# DI_DO.net
KiCad netlist of a schematic drawn in Altium Designer
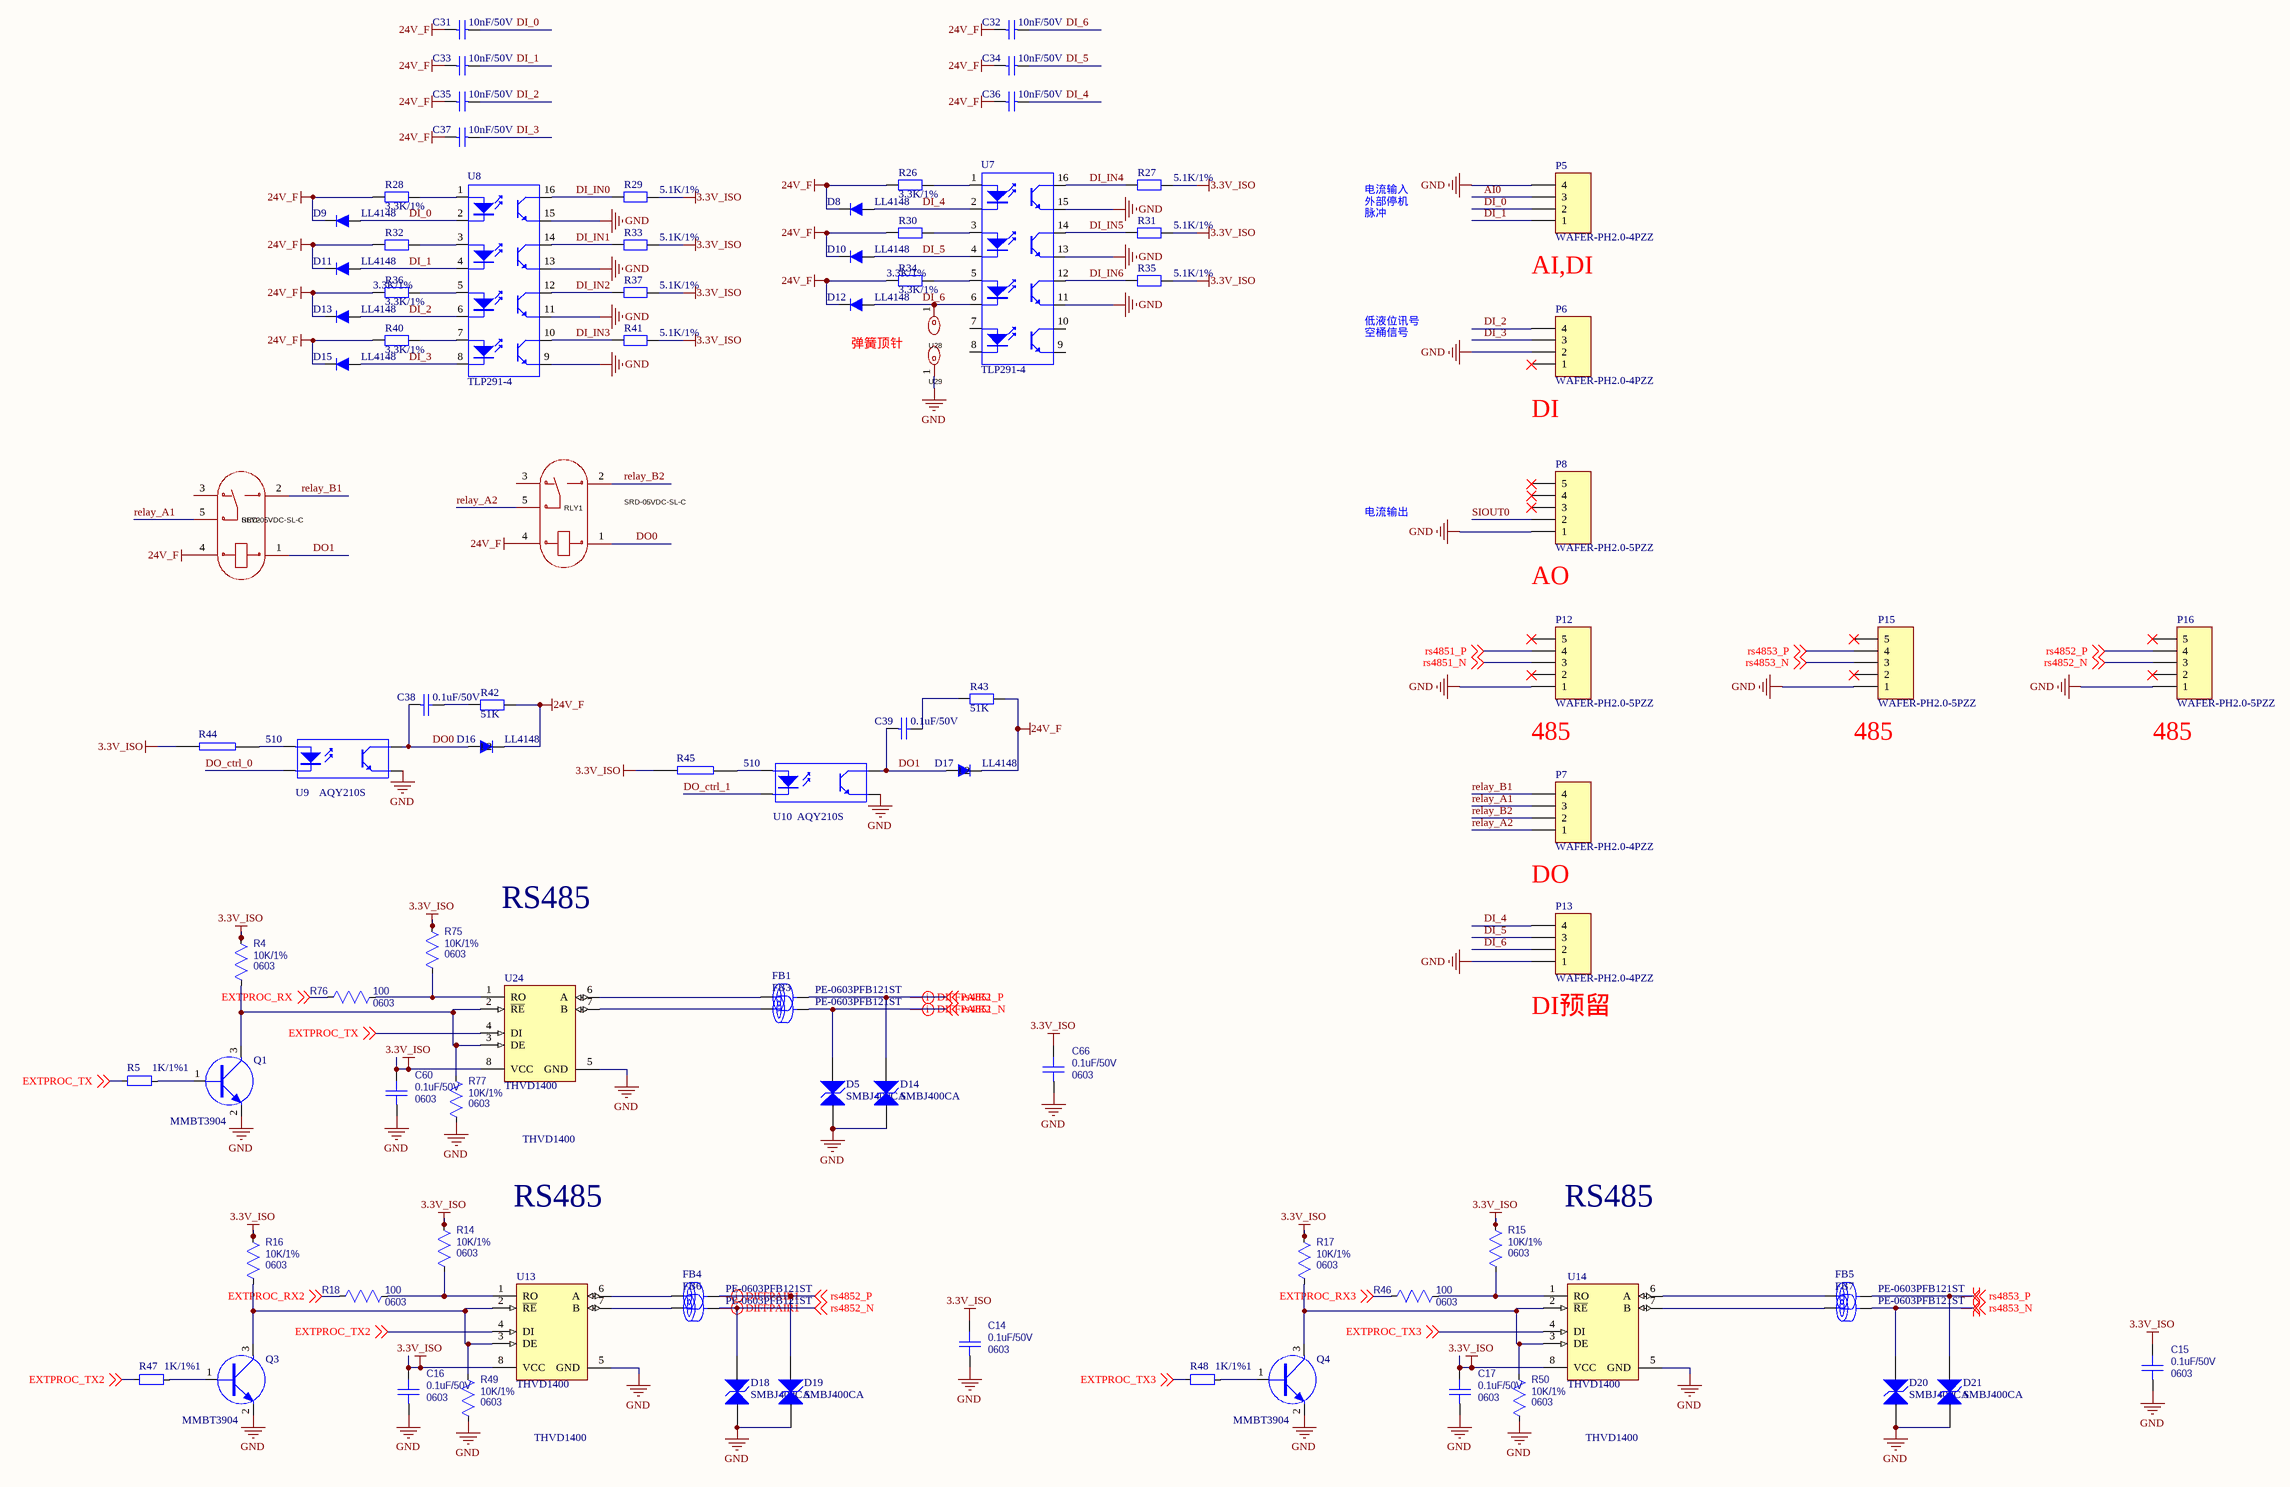
[diagram p0: DI_DO.SchDoc]

(export (version "E")
  (design (tool "Eeschema 10.0.6"))
  (components
    (comp (ref "C14")
      (value "0.1uF/50V")
      (footprint "0603C")
      (description "Capacitor, MLCC")
      (fields (field (name "PACKAGE") "0603"))
      (libsource (lib "Karl") (part "Capacitor_0603"))
    )
    (comp (ref "C15")
      (value "0.1uF/50V")
      (footprint "0603C")
      (description "Capacitor, MLCC")
      (fields (field (name "PACKAGE") "0603"))
      (libsource (lib "Karl") (part "Capacitor_0603"))
    )
    (comp (ref "C16")
      (value "0.1uF/50V")
      (footprint "0603C")
      (description "Capacitor, MLCC")
      (fields (field (name "PACKAGE") "0603"))
      (libsource (lib "Karl") (part "Capacitor_0603"))
    )
    (comp (ref "C17")
      (value "0.1uF/50V")
      (footprint "0603C")
      (description "Capacitor, MLCC")
      (fields (field (name "PACKAGE") "0603"))
      (libsource (lib "Karl") (part "Capacitor_0603"))
    )
    (comp (ref "C31")
      (value "10nF/50V")
      (footprint "0603C")
      (description "Capacitor")
      (libsource (lib "Miscellaneous Devices") (part "Cap"))
    )
    (comp (ref "C32")
      (value "10nF/50V")
      (footprint "0603C")
      (description "Capacitor")
      (libsource (lib "Miscellaneous Devices") (part "Cap"))
    )
    (comp (ref "C33")
      (value "10nF/50V")
      (footprint "0603C")
      (description "Capacitor")
      (libsource (lib "Miscellaneous Devices") (part "Cap"))
    )
    (comp (ref "C34")
      (value "10nF/50V")
      (footprint "0603C")
      (description "Capacitor")
      (libsource (lib "Miscellaneous Devices") (part "Cap"))
    )
    (comp (ref "C35")
      (value "10nF/50V")
      (footprint "0603C")
      (description "Capacitor")
      (libsource (lib "Miscellaneous Devices") (part "Cap"))
    )
    (comp (ref "C36")
      (value "10nF/50V")
      (footprint "0603C")
      (description "Capacitor")
      (libsource (lib "Miscellaneous Devices") (part "Cap"))
    )
    (comp (ref "C37")
      (value "10nF/50V")
      (footprint "0603C")
      (description "Capacitor")
      (libsource (lib "Miscellaneous Devices") (part "Cap"))
    )
    (comp (ref "C38")
      (value "0.1uF/50V")
      (footprint "0603C")
      (description "Capacitor")
      (libsource (lib "*") (part "CAP"))
    )
    (comp (ref "C39")
      (value "0.1uF/50V")
      (footprint "0603C")
      (description "Capacitor")
      (libsource (lib "*") (part "CAP"))
    )
    (comp (ref "C60")
      (value "0.1uF/50V")
      (footprint "0603C")
      (description "Capacitor, MLCC")
      (fields (field (name "PACKAGE") "0603"))
      (libsource (lib "Karl") (part "Capacitor_0603"))
    )
    (comp (ref "C66")
      (value "0.1uF/50V")
      (footprint "0603C")
      (description "Capacitor, MLCC")
      (fields (field (name "PACKAGE") "0603"))
      (libsource (lib "Karl") (part "Capacitor_0603"))
    )
    (comp (ref "D5")
      (value "SMBJ400CA")
      (footprint "SMB")
      (description "Transient Voltage Suppression Diode, 400 W, 33 V, -65 to 150 degC, 2-Pin SMD, RoHS, Tape and Reel")
      (libsource (lib "Bogen") (part "SMAJ12CA"))
    )
    (comp (ref "D8")
      (value "LL4148")
      (footprint "DO-213AB/LL34/MiniMELF")
      (description "VISHAY,LL4148,圆柱体MiniMELF100V/2A,ROHS")
      (libsource (lib "") (part "LL4148_1"))
    )
    (comp (ref "D9")
      (value "LL4148")
      (footprint "DO-213AB/LL34/MiniMELF")
      (description "VISHAY,LL4148,圆柱体MiniMELF100V/2A,ROHS")
      (libsource (lib "") (part "LL4148_1"))
    )
    (comp (ref "D10")
      (value "LL4148")
      (footprint "DO-213AB/LL34/MiniMELF")
      (description "VISHAY,LL4148,圆柱体MiniMELF100V/2A,ROHS")
      (libsource (lib "") (part "LL4148_1"))
    )
    (comp (ref "D11")
      (value "LL4148")
      (footprint "DO-213AB/LL34/MiniMELF")
      (description "VISHAY,LL4148,圆柱体MiniMELF100V/2A,ROHS")
      (libsource (lib "") (part "LL4148_1"))
    )
    (comp (ref "D12")
      (value "LL4148")
      (footprint "DO-213AB/LL34/MiniMELF")
      (description "VISHAY,LL4148,圆柱体MiniMELF100V/2A,ROHS")
      (libsource (lib "") (part "LL4148_1"))
    )
    (comp (ref "D13")
      (value "LL4148")
      (footprint "DO-213AB/LL34/MiniMELF")
      (description "VISHAY,LL4148,圆柱体MiniMELF100V/2A,ROHS")
      (libsource (lib "") (part "LL4148_1"))
    )
    (comp (ref "D14")
      (value "SMBJ400CA")
      (footprint "SMB")
      (description "Transient Voltage Suppression Diode, 400 W, 33 V, -65 to 150 degC, 2-Pin SMD, RoHS, Tape and Reel")
      (libsource (lib "Bogen") (part "SMAJ12CA"))
    )
    (comp (ref "D15")
      (value "LL4148")
      (footprint "DO-213AB/LL34/MiniMELF")
      (description "VISHAY,LL4148,圆柱体MiniMELF100V/2A,ROHS")
      (libsource (lib "") (part "LL4148_1"))
    )
    (comp (ref "D16")
      (value "LL4148")
      (footprint "DO-213AB/LL34/MiniMELF")
      (description "VISHAY,LL4148,圆柱体MiniMELF100V/2A,ROHS")
      (libsource (lib "Device2018") (part "LL4148"))
    )
    (comp (ref "D17")
      (value "LL4148")
      (footprint "DO-213AB/LL34/MiniMELF")
      (description "VISHAY,LL4148,圆柱体MiniMELF100V/2A,ROHS")
      (libsource (lib "Device2018") (part "LL4148"))
    )
    (comp (ref "D18")
      (value "SMBJ400CA")
      (footprint "SMB")
      (description "Transient Voltage Suppression Diode, 400 W, 33 V, -65 to 150 degC, 2-Pin SMD, RoHS, Tape and Reel")
      (libsource (lib "Bogen") (part "SMAJ12CA"))
    )
    (comp (ref "D19")
      (value "SMBJ400CA")
      (footprint "SMB")
      (description "Transient Voltage Suppression Diode, 400 W, 33 V, -65 to 150 degC, 2-Pin SMD, RoHS, Tape and Reel")
      (libsource (lib "Bogen") (part "SMAJ12CA"))
    )
    (comp (ref "D20")
      (value "SMBJ400CA")
      (footprint "SMB")
      (description "Transient Voltage Suppression Diode, 400 W, 33 V, -65 to 150 degC, 2-Pin SMD, RoHS, Tape and Reel")
      (libsource (lib "Bogen") (part "SMAJ12CA"))
    )
    (comp (ref "D21")
      (value "SMBJ400CA")
      (footprint "SMB")
      (description "Transient Voltage Suppression Diode, 400 W, 33 V, -65 to 150 degC, 2-Pin SMD, RoHS, Tape and Reel")
      (libsource (lib "Bogen") (part "SMAJ12CA"))
    )
    (comp (ref "FB1")
      (value "PE-0603PFB121ST")
      (footprint "FBC0603")
      (description "Ferrite Bead Chip")
      (libsource (lib "Karl") (part "FBC0603"))
    )
    (comp (ref "FB3")
      (value "PE-0603PFB121ST")
      (footprint "FBC0603")
      (description "Ferrite Bead Chip")
      (libsource (lib "Karl") (part "FBC0603"))
    )
    (comp (ref "FB4")
      (value "PE-0603PFB121ST")
      (footprint "FBC0603")
      (description "Ferrite Bead Chip")
      (libsource (lib "Karl") (part "FBC0603"))
    )
    (comp (ref "FB5")
      (value "PE-0603PFB121ST")
      (footprint "FBC0603")
      (description "Ferrite Bead Chip")
      (libsource (lib "Karl") (part "FBC0603"))
    )
    (comp (ref "FB6")
      (value "PE-0603PFB121ST")
      (footprint "FBC0603")
      (description "Ferrite Bead Chip")
      (libsource (lib "Karl") (part "FBC0603"))
    )
    (comp (ref "FB7")
      (value "PE-0603PFB121ST")
      (footprint "FBC0603")
      (description "Ferrite Bead Chip")
      (libsource (lib "Karl") (part "FBC0603"))
    )
    (comp (ref "P5")
      (value "WAFER-PH2.0-4PZZ")
      (footprint "CONN#PH2.0-4A")
      (description "Header, 4-Pin")
      (libsource (lib "Miscellaneous Connectors") (part "Header 4"))
    )
    (comp (ref "P6")
      (value "WAFER-PH2.0-4PZZ")
      (footprint "CONN#PH2.0-4A")
      (description "Header, 4-Pin")
      (libsource (lib "Miscellaneous Connectors") (part "Header 4"))
    )
    (comp (ref "P7")
      (value "WAFER-PH2.0-4PZZ")
      (footprint "CONN#PH2.0-4A")
      (description "Header, 4-Pin")
      (libsource (lib "Miscellaneous Connectors") (part "Header 4"))
    )
    (comp (ref "P8")
      (value "WAFER-PH2.0-5PZZ")
      (footprint "CONN#PH2.0-5A")
      (description "Header, 5-Pin")
      (libsource (lib "Miscellaneous Connectors") (part "Header 5"))
    )
    (comp (ref "P12")
      (value "WAFER-PH2.0-5PZZ")
      (footprint "CONN#PH2.0-5A")
      (description "Header, 5-Pin")
      (libsource (lib "Miscellaneous Connectors") (part "Header 5"))
    )
    (comp (ref "P13")
      (value "WAFER-PH2.0-4PZZ")
      (footprint "CONN#PH2.0-4A")
      (description "Header, 4-Pin")
      (libsource (lib "Miscellaneous Connectors") (part "Header 4"))
    )
    (comp (ref "P15")
      (value "WAFER-PH2.0-5PZZ")
      (footprint "CONN#PH2.0-5A")
      (description "Header, 5-Pin")
      (libsource (lib "Miscellaneous Connectors") (part "Header 5"))
    )
    (comp (ref "P16")
      (value "WAFER-PH2.0-5PZZ")
      (footprint "CONN#PH2.0-5A")
      (description "Header, 5-Pin")
      (libsource (lib "Miscellaneous Connectors") (part "Header 5"))
    )
    (comp (ref "Q1")
      (value "MMBT3904")
      (footprint "SOT23-3")
      (libsource (lib "CenLib") (part "NPN_MMBT3904"))
    )
    (comp (ref "Q3")
      (value "MMBT3904")
      (footprint "SOT23-3")
      (libsource (lib "CenLib") (part "NPN_MMBT3904"))
    )
    (comp (ref "Q4")
      (value "MMBT3904")
      (footprint "SOT23-3")
      (libsource (lib "CenLib") (part "NPN_MMBT3904"))
    )
    (comp (ref "R4")
      (value "10K/1%")
      (footprint "0603R")
      (description "Resistor, Standard")
      (fields (field (name "PACKAGE") "0603"))
      (libsource (lib "Karl") (part "Resistor_0603"))
    )
    (comp (ref "R5") (value "1K/1%1") (footprint "0603r") (libsource (lib "RC_M_D_00") (part "RES0603")))
    (comp (ref "R14")
      (value "10K/1%")
      (footprint "0603R")
      (description "Resistor, Standard")
      (fields (field (name "PACKAGE") "0603"))
      (libsource (lib "Karl") (part "Resistor_0603"))
    )
    (comp (ref "R15")
      (value "10K/1%")
      (footprint "0603R")
      (description "Resistor, Standard")
      (fields (field (name "PACKAGE") "0603"))
      (libsource (lib "Karl") (part "Resistor_0603"))
    )
    (comp (ref "R16")
      (value "10K/1%")
      (footprint "0603R")
      (description "Resistor, Standard")
      (fields (field (name "PACKAGE") "0603"))
      (libsource (lib "Karl") (part "Resistor_0603"))
    )
    (comp (ref "R17")
      (value "10K/1%")
      (footprint "0603R")
      (description "Resistor, Standard")
      (fields (field (name "PACKAGE") "0603"))
      (libsource (lib "Karl") (part "Resistor_0603"))
    )
    (comp (ref "R18")
      (value "100")
      (footprint "0603R")
      (description "Resistor, Standard")
      (fields (field (name "PACKAGE") "0603"))
      (libsource (lib "Karl") (part "Resistor_0603"))
    )
    (comp (ref "R26") (value "3.3K/1%") (footprint "0603R") (libsource (lib "MQlibrary") (part "Res0805M")))
    (comp (ref "R27") (value "5.1K/1%") (footprint "0603R") (libsource (lib "MQlibrary") (part "Res0805M")))
    (comp (ref "R28") (value "3.3K/1%") (footprint "0603R") (libsource (lib "MQlibrary") (part "Res0805M")))
    (comp (ref "R29") (value "5.1K/1%") (footprint "0603R") (libsource (lib "MQlibrary") (part "Res0805M")))
    (comp (ref "R30") (value "3.3K/1%") (footprint "0603R") (libsource (lib "MQlibrary") (part "Res0805M")))
    (comp (ref "R31") (value "5.1K/1%") (footprint "0603R") (libsource (lib "MQlibrary") (part "Res0805M")))
    (comp (ref "R32") (value "3.3K/1%") (footprint "0603R") (libsource (lib "MQlibrary") (part "Res0805M")))
    (comp (ref "R33") (value "5.1K/1%") (footprint "0603R") (libsource (lib "MQlibrary") (part "Res0805M")))
    (comp (ref "R34") (value "3.3K/1%") (footprint "0603R") (libsource (lib "MQlibrary") (part "Res0805M")))
    (comp (ref "R35") (value "5.1K/1%") (footprint "0603R") (libsource (lib "MQlibrary") (part "Res0805M")))
    (comp (ref "R36") (value "3.3K/1%") (footprint "0603R") (libsource (lib "MQlibrary") (part "Res0805M")))
    (comp (ref "R37") (value "5.1K/1%") (footprint "0603R") (libsource (lib "MQlibrary") (part "Res0805M")))
    (comp (ref "R40") (value "3.3K/1%") (footprint "0603R") (libsource (lib "MQlibrary") (part "Res0805M")))
    (comp (ref "R41") (value "5.1K/1%") (footprint "0603R") (libsource (lib "MQlibrary") (part "Res0805M")))
    (comp (ref "R42") (value "51K") (footprint "0603R") (libsource (lib "") (part "Res0805M_1")))
    (comp (ref "R43") (value "51K") (footprint "0603R") (libsource (lib "") (part "Res0805M_1")))
    (comp (ref "R44") (value "510") (footprint "0603R") (libsource (lib "*") (part "RES2")))
    (comp (ref "R45") (value "510") (footprint "0603R") (libsource (lib "*") (part "RES2")))
    (comp (ref "R46")
      (value "100")
      (footprint "0603R")
      (description "Resistor, Standard")
      (fields (field (name "PACKAGE") "0603"))
      (libsource (lib "Karl") (part "Resistor_0603"))
    )
    (comp (ref "R47") (value "1K/1%1") (footprint "0603r") (libsource (lib "RC_M_D_00") (part "RES0603")))
    (comp (ref "R48") (value "1K/1%1") (footprint "0603r") (libsource (lib "RC_M_D_00") (part "RES0603")))
    (comp (ref "R49")
      (value "10K/1%")
      (footprint "0603R")
      (description "Resistor, Standard")
      (fields (field (name "PACKAGE") "0603"))
      (libsource (lib "Karl") (part "Resistor_0603"))
    )
    (comp (ref "R50")
      (value "10K/1%")
      (footprint "0603R")
      (description "Resistor, Standard")
      (fields (field (name "PACKAGE") "0603"))
      (libsource (lib "Karl") (part "Resistor_0603"))
    )
    (comp (ref "R75")
      (value "10K/1%")
      (footprint "0603R")
      (description "Resistor, Standard")
      (fields (field (name "PACKAGE") "0603"))
      (libsource (lib "Karl") (part "Resistor_0603"))
    )
    (comp (ref "R76")
      (value "100")
      (footprint "0603R")
      (description "Resistor, Standard")
      (fields (field (name "PACKAGE") "0603"))
      (libsource (lib "Karl") (part "Resistor_0603"))
    )
    (comp (ref "R77")
      (value "10K/1%")
      (footprint "0603R")
      (description "Resistor, Standard")
      (fields (field (name "PACKAGE") "0603"))
      (libsource (lib "Karl") (part "Resistor_0603"))
    )
    (comp (ref "RLY1")
      (value "SRD-05VDC-SL-C")
      (footprint "RELAY-TH_SRD-XXVDC-XL-C")
      (libsource (lib "altium-import") (part "root_0_SRD-05VDC-SL-C_"))
    )
    (comp (ref "RLY2")
      (value "SRD-05VDC-SL-C")
      (footprint "RELAY-TH_SRD-XXVDC-XL-C")
      (libsource (lib "altium-import") (part "root_0_SRD-05VDC-SL-C_"))
    )
    (comp (ref "U7") (value "TLP291-4") (footprint "SOP16-T") (libsource (lib "DI16") (part "TLP281-4")))
    (comp (ref "U8") (value "TLP291-4") (footprint "SOP16-T") (libsource (lib "DI16") (part "TLP281-4")))
    (comp (ref "U9")
      (value "AQY210S")
      (footprint "sop4")
      (description "4-Pin Phototransistor Optocoupler")
      (libsource (lib "Miscellaneous Devices") (part "Optoisolator1"))
    )
    (comp (ref "U10")
      (value "AQY210S")
      (footprint "sop4")
      (description "4-Pin Phototransistor Optocoupler")
      (libsource (lib "Miscellaneous Devices") (part "Optoisolator1"))
    )
    (comp (ref "U13")
      (value "THVD1400")
      (footprint "MAXM-S8+4_M")
      (libsource (lib "Bogen") (part "MAX33071EASA+"))
    )
    (comp (ref "U14")
      (value "THVD1400")
      (footprint "MAXM-S8+4_M")
      (libsource (lib "Bogen") (part "MAX33071EASA+"))
    )
    (comp (ref "U24")
      (value "THVD1400")
      (footprint "MAXM-S8+4_M")
      (libsource (lib "Bogen") (part "MAX33071EASA+"))
    )
    (comp (ref "U28")
      (value "~")
      (footprint "CONN-SMD_YTC1P-3015-01")
      (libsource (lib "Flow_Pump") (part "YTC1P-3015-01"))
    )
    (comp (ref "U29")
      (value "~")
      (footprint "CONN-SMD_YTC1P-3015-01")
      (libsource (lib "Flow_Pump") (part "YTC1P-3015-01"))
    )
  )
  (nets
    (net (code "1") (name "/AI0") (class "Default")
      (node (ref "P5") (pin "3") (pinfunction "3_3") (pintype "passive"))
    )
    (net (code "2") (name "/DI_0") (class "Default")
      (node (ref "C31") (pin "2") (pinfunction "2_2") (pintype "passive"))
      (node (ref "D9") (pin "1") (pinfunction "2_1") (pintype "passive"))
      (node (ref "P5") (pin "2") (pinfunction "2_2") (pintype "passive"))
      (node (ref "U8") (pin "2") (pinfunction "K_2") (pintype "passive"))
    )
    (net (code "3") (name "/DI_1") (class "Default")
      (node (ref "C33") (pin "2") (pinfunction "2_2") (pintype "passive"))
      (node (ref "D11") (pin "1") (pinfunction "2_1") (pintype "passive"))
      (node (ref "P5") (pin "1") (pinfunction "1_1") (pintype "passive"))
      (node (ref "U8") (pin "4") (pinfunction "K_4") (pintype "passive"))
    )
    (net (code "4") (name "/DI_2") (class "Default")
      (node (ref "C35") (pin "2") (pinfunction "2_2") (pintype "passive"))
      (node (ref "D13") (pin "1") (pinfunction "2_1") (pintype "passive"))
      (node (ref "P6") (pin "4") (pinfunction "4_4") (pintype "passive"))
      (node (ref "U8") (pin "6") (pinfunction "K_6") (pintype "passive"))
    )
    (net (code "5") (name "/DI_3") (class "Default")
      (node (ref "C37") (pin "2") (pinfunction "2_2") (pintype "passive"))
      (node (ref "D15") (pin "1") (pinfunction "2_1") (pintype "passive"))
      (node (ref "P6") (pin "3") (pinfunction "3_3") (pintype "passive"))
      (node (ref "U8") (pin "8") (pinfunction "K_8") (pintype "passive"))
    )
    (net (code "6") (name "/DI_4") (class "Default")
      (node (ref "C36") (pin "2") (pinfunction "2_2") (pintype "passive"))
      (node (ref "D8") (pin "1") (pinfunction "2_1") (pintype "passive"))
      (node (ref "P13") (pin "4") (pinfunction "4_4") (pintype "passive"))
      (node (ref "U7") (pin "2") (pinfunction "K_2") (pintype "passive"))
    )
    (net (code "7") (name "/DI_5") (class "Default")
      (node (ref "C34") (pin "2") (pinfunction "2_2") (pintype "passive"))
      (node (ref "D10") (pin "1") (pinfunction "2_1") (pintype "passive"))
      (node (ref "P13") (pin "3") (pinfunction "3_3") (pintype "passive"))
      (node (ref "U7") (pin "4") (pinfunction "K_4") (pintype "passive"))
    )
    (net (code "8") (name "/DI_6") (class "Default")
      (node (ref "C32") (pin "2") (pinfunction "2_2") (pintype "passive"))
      (node (ref "D12") (pin "1") (pinfunction "2_1") (pintype "passive"))
      (node (ref "P13") (pin "2") (pinfunction "2_2") (pintype "passive"))
      (node (ref "U28") (pin "1") (pinfunction "1_1") (pintype "passive"))
      (node (ref "U7") (pin "6") (pinfunction "K_6") (pintype "passive"))
    )
    (net (code "9") (name "/DI_IN0") (class "Default")
      (node (ref "R29") (pin "2") (pinfunction "2_2") (pintype "passive"))
      (node (ref "U8") (pin "16") (pinfunction "C_16") (pintype "passive"))
    )
    (net (code "10") (name "/DI_IN1") (class "Default")
      (node (ref "R33") (pin "2") (pinfunction "2_2") (pintype "passive"))
      (node (ref "U8") (pin "14") (pinfunction "C_14") (pintype "passive"))
    )
    (net (code "11") (name "/DI_IN2") (class "Default")
      (node (ref "R37") (pin "2") (pinfunction "2_2") (pintype "passive"))
      (node (ref "U8") (pin "12") (pinfunction "C_12") (pintype "passive"))
    )
    (net (code "12") (name "/DI_IN3") (class "Default")
      (node (ref "R41") (pin "2") (pinfunction "2_2") (pintype "passive"))
      (node (ref "U8") (pin "10") (pinfunction "C_10") (pintype "passive"))
    )
    (net (code "13") (name "/DI_IN4") (class "Default")
      (node (ref "R27") (pin "2") (pinfunction "2_2") (pintype "passive"))
      (node (ref "U7") (pin "16") (pinfunction "C_16") (pintype "passive"))
    )
    (net (code "14") (name "/DI_IN5") (class "Default")
      (node (ref "R31") (pin "2") (pinfunction "2_2") (pintype "passive"))
      (node (ref "U7") (pin "14") (pinfunction "C_14") (pintype "passive"))
    )
    (net (code "15") (name "/DI_IN6") (class "Default")
      (node (ref "R35") (pin "2") (pinfunction "2_2") (pintype "passive"))
      (node (ref "U7") (pin "12") (pinfunction "C_12") (pintype "passive"))
    )
    (net (code "16") (name "/DO0") (class "Default")
      (node (ref "C38") (pin "1") (pinfunction "1_1") (pintype "passive"))
      (node (ref "D16") (pin "1") (pinfunction "2_1") (pintype "passive"))
      (node (ref "RLY1") (pin "1") (pinfunction "1_1") (pintype "passive"))
      (node (ref "U9") (pin "4") (pinfunction "C_4") (pintype "passive"))
    )
    (net (code "17") (name "/DO1") (class "Default")
      (node (ref "C39") (pin "1") (pinfunction "1_1") (pintype "passive"))
      (node (ref "D17") (pin "1") (pinfunction "2_1") (pintype "passive"))
      (node (ref "RLY2") (pin "1") (pinfunction "1_1") (pintype "passive"))
      (node (ref "U10") (pin "4") (pinfunction "C_4") (pintype "passive"))
    )
    (net (code "18") (name "/DO_ctrl_0") (class "Default")
      (node (ref "U9") (pin "2") (pinfunction "K_2") (pintype "passive"))
    )
    (net (code "19") (name "/DO_ctrl_1") (class "Default")
      (node (ref "U10") (pin "2") (pinfunction "K_2") (pintype "passive"))
    )
    (net (code "20") (name "/SIOUT0") (class "Default")
      (node (ref "P8") (pin "2") (pinfunction "2_2") (pintype "passive"))
    )
    (net (code "21") (name "/relay_A1") (class "Default")
      (node (ref "P7") (pin "3") (pinfunction "3_3") (pintype "passive"))
      (node (ref "RLY2") (pin "5") (pinfunction "5_5") (pintype "passive"))
    )
    (net (code "22") (name "/relay_A2") (class "Default")
      (node (ref "P7") (pin "1") (pinfunction "1_1") (pintype "passive"))
      (node (ref "RLY1") (pin "5") (pinfunction "5_5") (pintype "passive"))
    )
    (net (code "23") (name "/relay_B1") (class "Default")
      (node (ref "P7") (pin "4") (pinfunction "4_4") (pintype "passive"))
      (node (ref "RLY2") (pin "2") (pinfunction "2_2") (pintype "passive"))
    )
    (net (code "24") (name "/relay_B2") (class "Default")
      (node (ref "P7") (pin "2") (pinfunction "2_2") (pintype "passive"))
      (node (ref "RLY1") (pin "2") (pinfunction "2_2") (pintype "passive"))
    )
    (net (code "25") (name "3.3V_ISO") (class "Default")
      (node (ref "C14") (pin "1") (pinfunction "1_1") (pintype "passive"))
      (node (ref "C15") (pin "1") (pinfunction "1_1") (pintype "passive"))
      (node (ref "C16") (pin "1") (pinfunction "1_1") (pintype "passive"))
      (node (ref "C17") (pin "1") (pinfunction "1_1") (pintype "passive"))
      (node (ref "C60") (pin "1") (pinfunction "1_1") (pintype "passive"))
      (node (ref "C66") (pin "1") (pinfunction "1_1") (pintype "passive"))
      (node (ref "R14") (pin "2") (pinfunction "2_2") (pintype "passive"))
      (node (ref "R15") (pin "2") (pinfunction "2_2") (pintype "passive"))
      (node (ref "R16") (pin "2") (pinfunction "2_2") (pintype "passive"))
      (node (ref "R17") (pin "2") (pinfunction "2_2") (pintype "passive"))
      (node (ref "R27") (pin "1") (pinfunction "1_1") (pintype "passive"))
      (node (ref "R29") (pin "1") (pinfunction "1_1") (pintype "passive"))
      (node (ref "R31") (pin "1") (pinfunction "1_1") (pintype "passive"))
      (node (ref "R33") (pin "1") (pinfunction "1_1") (pintype "passive"))
      (node (ref "R35") (pin "1") (pinfunction "1_1") (pintype "passive"))
      (node (ref "R37") (pin "1") (pinfunction "1_1") (pintype "passive"))
      (node (ref "R4") (pin "2") (pinfunction "2_2") (pintype "passive"))
      (node (ref "R41") (pin "1") (pinfunction "1_1") (pintype "passive"))
      (node (ref "R44") (pin "2") (pinfunction "2_2") (pintype "passive"))
      (node (ref "R45") (pin "2") (pinfunction "2_2") (pintype "passive"))
      (node (ref "R75") (pin "2") (pinfunction "2_2") (pintype "passive"))
      (node (ref "U13") (pin "8") (pinfunction "VCC_8") (pintype "power_in"))
      (node (ref "U14") (pin "8") (pinfunction "VCC_8") (pintype "power_in"))
      (node (ref "U24") (pin "8") (pinfunction "VCC_8") (pintype "power_in"))
    )
    (net (code "26") (name "24V_F") (class "Default")
      (node (ref "C31") (pin "1") (pinfunction "1_1") (pintype "passive"))
      (node (ref "C32") (pin "1") (pinfunction "1_1") (pintype "passive"))
      (node (ref "C33") (pin "1") (pinfunction "1_1") (pintype "passive"))
      (node (ref "C34") (pin "1") (pinfunction "1_1") (pintype "passive"))
      (node (ref "C35") (pin "1") (pinfunction "1_1") (pintype "passive"))
      (node (ref "C36") (pin "1") (pinfunction "1_1") (pintype "passive"))
      (node (ref "C37") (pin "1") (pinfunction "1_1") (pintype "passive"))
      (node (ref "D10") (pin "2") (pinfunction "1_2") (pintype "passive"))
      (node (ref "D11") (pin "2") (pinfunction "1_2") (pintype "passive"))
      (node (ref "D12") (pin "2") (pinfunction "1_2") (pintype "passive"))
      (node (ref "D13") (pin "2") (pinfunction "1_2") (pintype "passive"))
      (node (ref "D15") (pin "2") (pinfunction "1_2") (pintype "passive"))
      (node (ref "D16") (pin "2") (pinfunction "1_2") (pintype "passive"))
      (node (ref "D17") (pin "2") (pinfunction "1_2") (pintype "passive"))
      (node (ref "D8") (pin "2") (pinfunction "1_2") (pintype "passive"))
      (node (ref "D9") (pin "2") (pinfunction "1_2") (pintype "passive"))
      (node (ref "R26") (pin "2") (pinfunction "2_2") (pintype "passive"))
      (node (ref "R28") (pin "2") (pinfunction "2_2") (pintype "passive"))
      (node (ref "R30") (pin "2") (pinfunction "2_2") (pintype "passive"))
      (node (ref "R32") (pin "2") (pinfunction "2_2") (pintype "passive"))
      (node (ref "R34") (pin "2") (pinfunction "2_2") (pintype "passive"))
      (node (ref "R36") (pin "2") (pinfunction "2_2") (pintype "passive"))
      (node (ref "R40") (pin "2") (pinfunction "2_2") (pintype "passive"))
      (node (ref "R42") (pin "2") (pinfunction "2_2") (pintype "passive"))
      (node (ref "R43") (pin "2") (pinfunction "2_2") (pintype "passive"))
      (node (ref "RLY1") (pin "4") (pinfunction "4_4") (pintype "passive"))
      (node (ref "RLY2") (pin "4") (pinfunction "4_4") (pintype "passive"))
    )
    (net (code "27") (name "EXTPROC_RX") (class "Default")
      (node (ref "R76") (pin "2") (pinfunction "2_2") (pintype "passive"))
    )
    (net (code "28") (name "EXTPROC_RX2") (class "Default")
      (node (ref "R18") (pin "2") (pinfunction "2_2") (pintype "passive"))
    )
    (net (code "29") (name "EXTPROC_RX3") (class "Default")
      (node (ref "R46") (pin "2") (pinfunction "2_2") (pintype "passive"))
    )
    (net (code "30") (name "EXTPROC_TX") (class "Default")
      (node (ref "R5") (pin "1") (pinfunction "1_1") (pintype "passive"))
      (node (ref "U24") (pin "4") (pinfunction "DI_4") (pintype "input"))
    )
    (net (code "31") (name "EXTPROC_TX2") (class "Default")
      (node (ref "R47") (pin "1") (pinfunction "1_1") (pintype "passive"))
      (node (ref "U13") (pin "4") (pinfunction "DI_4") (pintype "input"))
    )
    (net (code "32") (name "EXTPROC_TX3") (class "Default")
      (node (ref "R48") (pin "1") (pinfunction "1_1") (pintype "passive"))
      (node (ref "U14") (pin "4") (pinfunction "DI_4") (pintype "input"))
    )
    (net (code "33") (name "GND") (class "Default")
      (node (ref "C14") (pin "2") (pinfunction "2_2") (pintype "passive"))
      (node (ref "C15") (pin "2") (pinfunction "2_2") (pintype "passive"))
      (node (ref "C16") (pin "2") (pinfunction "2_2") (pintype "passive"))
      (node (ref "C17") (pin "2") (pinfunction "2_2") (pintype "passive"))
      (node (ref "C60") (pin "2") (pinfunction "2_2") (pintype "passive"))
      (node (ref "C66") (pin "2") (pinfunction "2_2") (pintype "passive"))
      (node (ref "D14") (pin "1") (pinfunction "A_1") (pintype "passive"))
      (node (ref "D18") (pin "1") (pinfunction "A_1") (pintype "passive"))
      (node (ref "D19") (pin "1") (pinfunction "A_1") (pintype "passive"))
      (node (ref "D20") (pin "1") (pinfunction "A_1") (pintype "passive"))
      (node (ref "D21") (pin "1") (pinfunction "A_1") (pintype "passive"))
      (node (ref "D5") (pin "1") (pinfunction "A_1") (pintype "passive"))
      (node (ref "P12") (pin "1") (pinfunction "1_1") (pintype "passive"))
      (node (ref "P13") (pin "1") (pinfunction "1_1") (pintype "passive"))
      (node (ref "P15") (pin "1") (pinfunction "1_1") (pintype "passive"))
      (node (ref "P16") (pin "1") (pinfunction "1_1") (pintype "passive"))
      (node (ref "P5") (pin "4") (pinfunction "4_4") (pintype "passive"))
      (node (ref "P6") (pin "2") (pinfunction "2_2") (pintype "passive"))
      (node (ref "P8") (pin "1") (pinfunction "1_1") (pintype "passive"))
      (node (ref "Q1") (pin "2") (pinfunction "E_2") (pintype "passive"))
      (node (ref "Q3") (pin "2") (pinfunction "E_2") (pintype "passive"))
      (node (ref "Q4") (pin "2") (pinfunction "E_2") (pintype "passive"))
      (node (ref "R49") (pin "1") (pinfunction "1_1") (pintype "passive"))
      (node (ref "R50") (pin "1") (pinfunction "1_1") (pintype "passive"))
      (node (ref "R77") (pin "1") (pinfunction "1_1") (pintype "passive"))
      (node (ref "U10") (pin "3") (pinfunction "E_3") (pintype "passive"))
      (node (ref "U13") (pin "5") (pinfunction "GND_5") (pintype "power_in"))
      (node (ref "U14") (pin "5") (pinfunction "GND_5") (pintype "power_in"))
      (node (ref "U24") (pin "5") (pinfunction "GND_5") (pintype "power_in"))
      (node (ref "U29") (pin "1") (pinfunction "1_1") (pintype "passive"))
      (node (ref "U7") (pin "11") (pinfunction "E_11") (pintype "passive"))
      (node (ref "U7") (pin "13") (pinfunction "E_13") (pintype "passive"))
      (node (ref "U7") (pin "15") (pinfunction "E_15") (pintype "passive"))
      (node (ref "U8") (pin "11") (pinfunction "E_11") (pintype "passive"))
      (node (ref "U8") (pin "13") (pinfunction "E_13") (pintype "passive"))
      (node (ref "U8") (pin "15") (pinfunction "E_15") (pintype "passive"))
      (node (ref "U8") (pin "9") (pinfunction "E_9") (pintype "passive"))
      (node (ref "U9") (pin "3") (pinfunction "E_3") (pintype "passive"))
    )
    (net (code "34") (name "Net-(C38-Pad2)") (class "Default")
      (node (ref "C38") (pin "2") (pinfunction "2_2") (pintype "passive"))
      (node (ref "R42") (pin "1") (pinfunction "1_1") (pintype "passive"))
    )
    (net (code "35") (name "Net-(C39-Pad2)") (class "Default")
      (node (ref "C39") (pin "2") (pinfunction "2_2") (pintype "passive"))
      (node (ref "R43") (pin "1") (pinfunction "1_1") (pintype "passive"))
    )
    (net (code "36") (name "Net-(Q1-B)") (class "Default")
      (node (ref "Q1") (pin "1") (pinfunction "B_1") (pintype "passive"))
      (node (ref "R5") (pin "2") (pinfunction "2_2") (pintype "passive"))
    )
    (net (code "37") (name "Net-(Q1-C)") (class "Default")
      (node (ref "Q1") (pin "3") (pinfunction "C_3") (pintype "passive"))
      (node (ref "R4") (pin "1") (pinfunction "1_1") (pintype "passive"))
      (node (ref "R77") (pin "2") (pinfunction "2_2") (pintype "passive"))
      (node (ref "U24") (pin "2") (pinfunction "~{RE}_2") (pintype "input"))
      (node (ref "U24") (pin "3") (pinfunction "DE_3") (pintype "input"))
    )
    (net (code "38") (name "Net-(Q3-B)") (class "Default")
      (node (ref "Q3") (pin "1") (pinfunction "B_1") (pintype "passive"))
      (node (ref "R47") (pin "2") (pinfunction "2_2") (pintype "passive"))
    )
    (net (code "39") (name "Net-(Q3-C)") (class "Default")
      (node (ref "Q3") (pin "3") (pinfunction "C_3") (pintype "passive"))
      (node (ref "R16") (pin "1") (pinfunction "1_1") (pintype "passive"))
      (node (ref "R49") (pin "2") (pinfunction "2_2") (pintype "passive"))
      (node (ref "U13") (pin "2") (pinfunction "~{RE}_2") (pintype "input"))
      (node (ref "U13") (pin "3") (pinfunction "DE_3") (pintype "input"))
    )
    (net (code "40") (name "Net-(Q4-B)") (class "Default")
      (node (ref "Q4") (pin "1") (pinfunction "B_1") (pintype "passive"))
      (node (ref "R48") (pin "2") (pinfunction "2_2") (pintype "passive"))
    )
    (net (code "41") (name "Net-(Q4-C)") (class "Default")
      (node (ref "Q4") (pin "3") (pinfunction "C_3") (pintype "passive"))
      (node (ref "R17") (pin "1") (pinfunction "1_1") (pintype "passive"))
      (node (ref "R50") (pin "2") (pinfunction "2_2") (pintype "passive"))
      (node (ref "U14") (pin "2") (pinfunction "~{RE}_2") (pintype "input"))
      (node (ref "U14") (pin "3") (pinfunction "DE_3") (pintype "input"))
    )
    (net (code "42") (name "Net-(R26-Pad1)") (class "Default")
      (node (ref "R26") (pin "1") (pinfunction "1_1") (pintype "passive"))
      (node (ref "U7") (pin "1") (pinfunction "A_1") (pintype "passive"))
    )
    (net (code "43") (name "Net-(R28-Pad1)") (class "Default")
      (node (ref "R28") (pin "1") (pinfunction "1_1") (pintype "passive"))
      (node (ref "U8") (pin "1") (pinfunction "A_1") (pintype "passive"))
    )
    (net (code "44") (name "Net-(R30-Pad1)") (class "Default")
      (node (ref "R30") (pin "1") (pinfunction "1_1") (pintype "passive"))
      (node (ref "U7") (pin "3") (pinfunction "A_3") (pintype "passive"))
    )
    (net (code "45") (name "Net-(R32-Pad1)") (class "Default")
      (node (ref "R32") (pin "1") (pinfunction "1_1") (pintype "passive"))
      (node (ref "U8") (pin "3") (pinfunction "A_3") (pintype "passive"))
    )
    (net (code "46") (name "Net-(R34-Pad1)") (class "Default")
      (node (ref "R34") (pin "1") (pinfunction "1_1") (pintype "passive"))
      (node (ref "U7") (pin "5") (pinfunction "A_5") (pintype "passive"))
    )
    (net (code "47") (name "Net-(R36-Pad1)") (class "Default")
      (node (ref "R36") (pin "1") (pinfunction "1_1") (pintype "passive"))
      (node (ref "U8") (pin "5") (pinfunction "A_5") (pintype "passive"))
    )
    (net (code "48") (name "Net-(R40-Pad1)") (class "Default")
      (node (ref "R40") (pin "1") (pinfunction "1_1") (pintype "passive"))
      (node (ref "U8") (pin "7") (pinfunction "A_7") (pintype "passive"))
    )
    (net (code "49") (name "Net-(U9-A)") (class "Default")
      (node (ref "R44") (pin "1") (pinfunction "1_1") (pintype "passive"))
      (node (ref "U9") (pin "1") (pinfunction "A_1") (pintype "passive"))
    )
    (net (code "50") (name "Net-(U10-A)") (class "Default")
      (node (ref "R45") (pin "1") (pinfunction "1_1") (pintype "passive"))
      (node (ref "U10") (pin "1") (pinfunction "A_1") (pintype "passive"))
    )
    (net (code "51") (name "Net-(U13-A)") (class "Default")
      (node (ref "FB4") (pin "1") (pinfunction "1_1") (pintype "passive"))
      (node (ref "U13") (pin "6") (pinfunction "A_6") (pintype "bidirectional"))
    )
    (net (code "52") (name "Net-(U13-B)") (class "Default")
      (node (ref "FB6") (pin "1") (pinfunction "1_1") (pintype "passive"))
      (node (ref "U13") (pin "7") (pinfunction "B_7") (pintype "bidirectional"))
    )
    (net (code "53") (name "Net-(U13-RO)") (class "Default")
      (node (ref "R14") (pin "1") (pinfunction "1_1") (pintype "passive"))
      (node (ref "R18") (pin "1") (pinfunction "1_1") (pintype "passive"))
      (node (ref "U13") (pin "1") (pinfunction "RO_1") (pintype "tri_state"))
    )
    (net (code "54") (name "Net-(U14-A)") (class "Default")
      (node (ref "FB5") (pin "1") (pinfunction "1_1") (pintype "passive"))
      (node (ref "U14") (pin "6") (pinfunction "A_6") (pintype "bidirectional"))
    )
    (net (code "55") (name "Net-(U14-B)") (class "Default")
      (node (ref "FB7") (pin "1") (pinfunction "1_1") (pintype "passive"))
      (node (ref "U14") (pin "7") (pinfunction "B_7") (pintype "bidirectional"))
    )
    (net (code "56") (name "Net-(U14-RO)") (class "Default")
      (node (ref "R15") (pin "1") (pinfunction "1_1") (pintype "passive"))
      (node (ref "R46") (pin "1") (pinfunction "1_1") (pintype "passive"))
      (node (ref "U14") (pin "1") (pinfunction "RO_1") (pintype "tri_state"))
    )
    (net (code "57") (name "Net-(U24-A)") (class "Default")
      (node (ref "FB1") (pin "1") (pinfunction "1_1") (pintype "passive"))
      (node (ref "U24") (pin "6") (pinfunction "A_6") (pintype "bidirectional"))
    )
    (net (code "58") (name "Net-(U24-B)") (class "Default")
      (node (ref "FB3") (pin "1") (pinfunction "1_1") (pintype "passive"))
      (node (ref "U24") (pin "7") (pinfunction "B_7") (pintype "bidirectional"))
    )
    (net (code "59") (name "Net-(U24-RO)") (class "Default")
      (node (ref "R75") (pin "1") (pinfunction "1_1") (pintype "passive"))
      (node (ref "R76") (pin "1") (pinfunction "1_1") (pintype "passive"))
      (node (ref "U24") (pin "1") (pinfunction "RO_1") (pintype "tri_state"))
    )
    (net (code "60") (name "rs4851_N") (class "Default")
      (node (ref "D5") (pin "2") (pinfunction "A_2") (pintype "passive"))
      (node (ref "FB3") (pin "2") (pinfunction "2_2") (pintype "passive"))
      (node (ref "P12") (pin "3") (pinfunction "3_3") (pintype "passive"))
    )
    (net (code "61") (name "rs4851_P") (class "Default")
      (node (ref "D14") (pin "2") (pinfunction "A_2") (pintype "passive"))
      (node (ref "FB1") (pin "2") (pinfunction "2_2") (pintype "passive"))
      (node (ref "P12") (pin "4") (pinfunction "4_4") (pintype "passive"))
    )
    (net (code "62") (name "rs4852_N") (class "Default")
      (node (ref "D18") (pin "2") (pinfunction "A_2") (pintype "passive"))
      (node (ref "FB6") (pin "2") (pinfunction "2_2") (pintype "passive"))
      (node (ref "P16") (pin "3") (pinfunction "3_3") (pintype "passive"))
    )
    (net (code "63") (name "rs4852_P") (class "Default")
      (node (ref "D19") (pin "2") (pinfunction "A_2") (pintype "passive"))
      (node (ref "FB4") (pin "2") (pinfunction "2_2") (pintype "passive"))
      (node (ref "P16") (pin "4") (pinfunction "4_4") (pintype "passive"))
    )
    (net (code "64") (name "rs4853_N") (class "Default")
      (node (ref "D20") (pin "2") (pinfunction "A_2") (pintype "passive"))
      (node (ref "FB7") (pin "2") (pinfunction "2_2") (pintype "passive"))
      (node (ref "P15") (pin "3") (pinfunction "3_3") (pintype "passive"))
    )
    (net (code "65") (name "rs4853_P") (class "Default")
      (node (ref "D21") (pin "2") (pinfunction "A_2") (pintype "passive"))
      (node (ref "FB5") (pin "2") (pinfunction "2_2") (pintype "passive"))
      (node (ref "P15") (pin "4") (pinfunction "4_4") (pintype "passive"))
    )
    (net (code "66") (name "unconnected-(P6-Pad1)") (class "Default")
      (node (ref "P6") (pin "1") (pinfunction "1_1") (pintype "passive+no_connect"))
    )
    (net (code "67") (name "unconnected-(P8-Pad3)") (class "Default")
      (node (ref "P8") (pin "3") (pinfunction "3_3") (pintype "passive+no_connect"))
    )
    (net (code "68") (name "unconnected-(P8-Pad4)") (class "Default")
      (node (ref "P8") (pin "4") (pinfunction "4_4") (pintype "passive+no_connect"))
    )
    (net (code "69") (name "unconnected-(P8-Pad5)") (class "Default")
      (node (ref "P8") (pin "5") (pinfunction "5_5") (pintype "passive+no_connect"))
    )
    (net (code "70") (name "unconnected-(P12-Pad2)") (class "Default")
      (node (ref "P12") (pin "2") (pinfunction "2_2") (pintype "passive+no_connect"))
    )
    (net (code "71") (name "unconnected-(P12-Pad5)") (class "Default")
      (node (ref "P12") (pin "5") (pinfunction "5_5") (pintype "passive+no_connect"))
    )
    (net (code "72") (name "unconnected-(P15-Pad2)") (class "Default")
      (node (ref "P15") (pin "2") (pinfunction "2_2") (pintype "passive+no_connect"))
    )
    (net (code "73") (name "unconnected-(P15-Pad5)") (class "Default")
      (node (ref "P15") (pin "5") (pinfunction "5_5") (pintype "passive+no_connect"))
    )
    (net (code "74") (name "unconnected-(P16-Pad2)") (class "Default")
      (node (ref "P16") (pin "2") (pinfunction "2_2") (pintype "passive+no_connect"))
    )
    (net (code "75") (name "unconnected-(P16-Pad5)") (class "Default")
      (node (ref "P16") (pin "5") (pinfunction "5_5") (pintype "passive+no_connect"))
    )
    (net (code "76") (name "unconnected-(RLY1-Pad3)") (class "Default")
      (node (ref "RLY1") (pin "3") (pinfunction "3_3") (pintype "passive"))
    )
    (net (code "77") (name "unconnected-(RLY2-Pad3)") (class "Default")
      (node (ref "RLY2") (pin "3") (pinfunction "3_3") (pintype "passive"))
    )
    (net (code "78") (name "unconnected-(U7-A-Pad7)") (class "Default")
      (node (ref "U7") (pin "7") (pinfunction "A_7") (pintype "passive"))
    )
    (net (code "79") (name "unconnected-(U7-C-Pad10)") (class "Default")
      (node (ref "U7") (pin "10") (pinfunction "C_10") (pintype "passive"))
    )
    (net (code "80") (name "unconnected-(U7-E-Pad9)") (class "Default")
      (node (ref "U7") (pin "9") (pinfunction "E_9") (pintype "passive"))
    )
    (net (code "81") (name "unconnected-(U7-K-Pad8)") (class "Default")
      (node (ref "U7") (pin "8") (pinfunction "K_8") (pintype "passive"))
    )
  )
)
